# eagle8.net
KiCad netlist of a schematic drawn in EAGLE
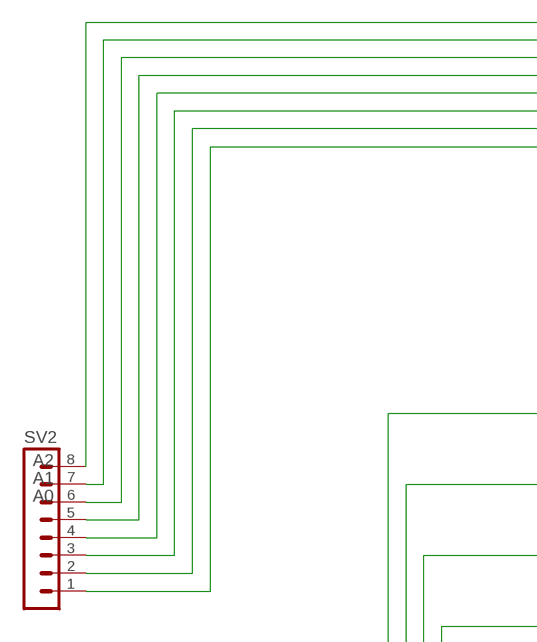
[diagram p0: schematic, sheet 1, part 1 of 3]
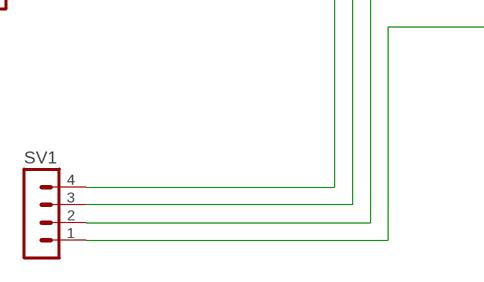
[diagram p1: schematic, sheet 1, part 2 of 3]
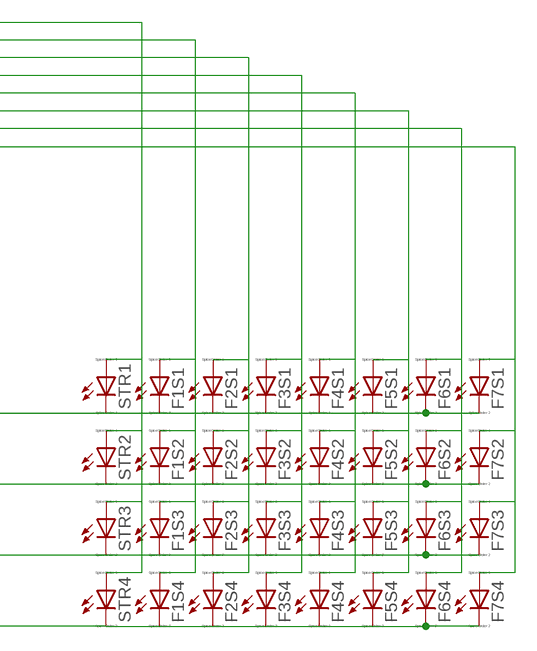
[diagram p2: schematic, sheet 1, part 3 of 3]

(export (version "E")
  (design (tool "Eeschema 10.0.6"))
  (components
    (comp (ref "F1S1")
      (value "LED_ESML0603")
      (footprint "eagle-import:LED_SML0603")
      (libsource (lib "eagle-import") (part "LED_ESML0603"))
    )
    (comp (ref "F1S2")
      (value "LED_ESML0603")
      (footprint "eagle-import:LED_SML0603")
      (libsource (lib "eagle-import") (part "LED_ESML0603"))
    )
    (comp (ref "F1S3")
      (value "LED_ESML0603")
      (footprint "eagle-import:LED_SML0603")
      (libsource (lib "eagle-import") (part "LED_ESML0603"))
    )
    (comp (ref "F1S4")
      (value "LED_ESML0603")
      (footprint "eagle-import:LED_SML0603")
      (libsource (lib "eagle-import") (part "LED_ESML0603"))
    )
    (comp (ref "F2S1")
      (value "LED_ESML0603")
      (footprint "eagle-import:LED_SML0603")
      (libsource (lib "eagle-import") (part "LED_ESML0603"))
    )
    (comp (ref "F2S2")
      (value "LED_ESML0603")
      (footprint "eagle-import:LED_SML0603")
      (libsource (lib "eagle-import") (part "LED_ESML0603"))
    )
    (comp (ref "F2S3")
      (value "LED_ESML0603")
      (footprint "eagle-import:LED_SML0603")
      (libsource (lib "eagle-import") (part "LED_ESML0603"))
    )
    (comp (ref "F2S4")
      (value "LED_ESML0603")
      (footprint "eagle-import:LED_SML0603")
      (libsource (lib "eagle-import") (part "LED_ESML0603"))
    )
    (comp (ref "F3S1")
      (value "LED_ESML0603")
      (footprint "eagle-import:LED_SML0603")
      (libsource (lib "eagle-import") (part "LED_ESML0603"))
    )
    (comp (ref "F3S2")
      (value "LED_ESML0603")
      (footprint "eagle-import:LED_SML0603")
      (libsource (lib "eagle-import") (part "LED_ESML0603"))
    )
    (comp (ref "F3S3")
      (value "LED_ESML0603")
      (footprint "eagle-import:LED_SML0603")
      (libsource (lib "eagle-import") (part "LED_ESML0603"))
    )
    (comp (ref "F3S4")
      (value "LED_ESML0603")
      (footprint "eagle-import:LED_SML0603")
      (libsource (lib "eagle-import") (part "LED_ESML0603"))
    )
    (comp (ref "F4S1")
      (value "LED_ESML0603")
      (footprint "eagle-import:LED_SML0603")
      (libsource (lib "eagle-import") (part "LED_ESML0603"))
    )
    (comp (ref "F4S2")
      (value "LED_ESML0603")
      (footprint "eagle-import:LED_SML0603")
      (libsource (lib "eagle-import") (part "LED_ESML0603"))
    )
    (comp (ref "F4S3")
      (value "LED_ESML0603")
      (footprint "eagle-import:LED_SML0603")
      (libsource (lib "eagle-import") (part "LED_ESML0603"))
    )
    (comp (ref "F4S4")
      (value "LED_ESML0603")
      (footprint "eagle-import:LED_SML0603")
      (libsource (lib "eagle-import") (part "LED_ESML0603"))
    )
    (comp (ref "F5S1")
      (value "LED_ESML0603")
      (footprint "eagle-import:LED_SML0603")
      (libsource (lib "eagle-import") (part "LED_ESML0603"))
    )
    (comp (ref "F5S2")
      (value "LED_ESML0603")
      (footprint "eagle-import:LED_SML0603")
      (libsource (lib "eagle-import") (part "LED_ESML0603"))
    )
    (comp (ref "F5S3")
      (value "LED_ESML0603")
      (footprint "eagle-import:LED_SML0603")
      (libsource (lib "eagle-import") (part "LED_ESML0603"))
    )
    (comp (ref "F5S4")
      (value "LED_ESML0603")
      (footprint "eagle-import:LED_SML0603")
      (libsource (lib "eagle-import") (part "LED_ESML0603"))
    )
    (comp (ref "F6S1")
      (value "LED_ESML0603")
      (footprint "eagle-import:LED_SML0603")
      (libsource (lib "eagle-import") (part "LED_ESML0603"))
    )
    (comp (ref "F6S2")
      (value "LED_ESML0603")
      (footprint "eagle-import:LED_SML0603")
      (libsource (lib "eagle-import") (part "LED_ESML0603"))
    )
    (comp (ref "F6S3")
      (value "LED_ESML0603")
      (footprint "eagle-import:LED_SML0603")
      (libsource (lib "eagle-import") (part "LED_ESML0603"))
    )
    (comp (ref "F6S4")
      (value "LED_ESML0603")
      (footprint "eagle-import:LED_SML0603")
      (libsource (lib "eagle-import") (part "LED_ESML0603"))
    )
    (comp (ref "F7S1")
      (value "LED_ESML0603")
      (footprint "eagle-import:LED_SML0603")
      (libsource (lib "eagle-import") (part "LED_ESML0603"))
    )
    (comp (ref "F7S2")
      (value "LED_ESML0603")
      (footprint "eagle-import:LED_SML0603")
      (libsource (lib "eagle-import") (part "LED_ESML0603"))
    )
    (comp (ref "F7S3")
      (value "LED_ESML0603")
      (footprint "eagle-import:LED_SML0603")
      (libsource (lib "eagle-import") (part "LED_ESML0603"))
    )
    (comp (ref "F7S4")
      (value "LED_ESML0603")
      (footprint "eagle-import:LED_SML0603")
      (libsource (lib "eagle-import") (part "LED_ESML0603"))
    )
    (comp (ref "STR1")
      (value "LED_ESML0603")
      (footprint "eagle-import:LED_SML0603")
      (libsource (lib "eagle-import") (part "LED_ESML0603"))
    )
    (comp (ref "STR2")
      (value "LED_ESML0603")
      (footprint "eagle-import:LED_SML0603")
      (libsource (lib "eagle-import") (part "LED_ESML0603"))
    )
    (comp (ref "STR3")
      (value "LED_ESML0603")
      (footprint "eagle-import:LED_SML0603")
      (libsource (lib "eagle-import") (part "LED_ESML0603"))
    )
    (comp (ref "STR4")
      (value "LED_ESML0603")
      (footprint "eagle-import:LED_SML0603")
      (libsource (lib "eagle-import") (part "LED_ESML0603"))
    )
    (comp (ref "SV1")
      (value "MA04-1")
      (footprint "eagle-import:MA04-1")
      (libsource (lib "eagle-import") (part "MA04-1"))
    )
    (comp (ref "SV2")
      (value "MA08-1")
      (footprint "eagle-import:MA08-1")
      (libsource (lib "eagle-import") (part "MA08-1"))
    )
  )
  (nets
    (net (code "1") (name "/A0") (class "Default")
      (node (ref "F2S1") (pin "A") (pinfunction "A_A") (pintype "passive"))
      (node (ref "F2S2") (pin "A") (pinfunction "A_A") (pintype "passive"))
      (node (ref "F2S3") (pin "A") (pinfunction "A_A") (pintype "passive"))
      (node (ref "F2S4") (pin "A") (pinfunction "A_A") (pintype "passive"))
      (node (ref "SV2") (pin "6") (pinfunction "6_6") (pintype "passive"))
    )
    (net (code "2") (name "/A1") (class "Default")
      (node (ref "F1S1") (pin "A") (pinfunction "A_A") (pintype "passive"))
      (node (ref "F1S2") (pin "A") (pinfunction "A_A") (pintype "passive"))
      (node (ref "F1S3") (pin "A") (pinfunction "A_A") (pintype "passive"))
      (node (ref "F1S4") (pin "A") (pinfunction "A_A") (pintype "passive"))
      (node (ref "SV2") (pin "7") (pinfunction "7_7") (pintype "passive"))
    )
    (net (code "3") (name "/A2") (class "Default")
      (node (ref "STR1") (pin "A") (pinfunction "A_A") (pintype "passive"))
      (node (ref "STR2") (pin "A") (pinfunction "A_A") (pintype "passive"))
      (node (ref "STR3") (pin "A") (pinfunction "A_A") (pintype "passive"))
      (node (ref "STR4") (pin "A") (pinfunction "A_A") (pintype "passive"))
      (node (ref "SV2") (pin "8") (pinfunction "8_8") (pintype "passive"))
    )
    (net (code "4") (name "Net-(F1S1-PadC)") (class "Default")
      (node (ref "F1S1") (pin "C") (pinfunction "C_C") (pintype "passive"))
      (node (ref "F2S1") (pin "C") (pinfunction "C_C") (pintype "passive"))
      (node (ref "F3S1") (pin "C") (pinfunction "C_C") (pintype "passive"))
      (node (ref "F4S1") (pin "C") (pinfunction "C_C") (pintype "passive"))
      (node (ref "F5S1") (pin "C") (pinfunction "C_C") (pintype "passive"))
      (node (ref "F6S1") (pin "C") (pinfunction "C_C") (pintype "passive"))
      (node (ref "F7S1") (pin "C") (pinfunction "C_C") (pintype "passive"))
      (node (ref "STR1") (pin "C") (pinfunction "C_C") (pintype "passive"))
      (node (ref "SV1") (pin "4") (pinfunction "4_4") (pintype "passive"))
    )
    (net (code "5") (name "Net-(F1S2-PadC)") (class "Default")
      (node (ref "F1S2") (pin "C") (pinfunction "C_C") (pintype "passive"))
      (node (ref "F2S2") (pin "C") (pinfunction "C_C") (pintype "passive"))
      (node (ref "F3S2") (pin "C") (pinfunction "C_C") (pintype "passive"))
      (node (ref "F4S2") (pin "C") (pinfunction "C_C") (pintype "passive"))
      (node (ref "F5S2") (pin "C") (pinfunction "C_C") (pintype "passive"))
      (node (ref "F6S2") (pin "C") (pinfunction "C_C") (pintype "passive"))
      (node (ref "F7S2") (pin "C") (pinfunction "C_C") (pintype "passive"))
      (node (ref "STR2") (pin "C") (pinfunction "C_C") (pintype "passive"))
      (node (ref "SV1") (pin "3") (pinfunction "3_3") (pintype "passive"))
    )
    (net (code "6") (name "Net-(F1S3-PadC)") (class "Default")
      (node (ref "F1S3") (pin "C") (pinfunction "C_C") (pintype "passive"))
      (node (ref "F2S3") (pin "C") (pinfunction "C_C") (pintype "passive"))
      (node (ref "F3S3") (pin "C") (pinfunction "C_C") (pintype "passive"))
      (node (ref "F4S3") (pin "C") (pinfunction "C_C") (pintype "passive"))
      (node (ref "F5S3") (pin "C") (pinfunction "C_C") (pintype "passive"))
      (node (ref "F6S3") (pin "C") (pinfunction "C_C") (pintype "passive"))
      (node (ref "F7S3") (pin "C") (pinfunction "C_C") (pintype "passive"))
      (node (ref "STR3") (pin "C") (pinfunction "C_C") (pintype "passive"))
      (node (ref "SV1") (pin "2") (pinfunction "2_2") (pintype "passive"))
    )
    (net (code "7") (name "Net-(F1S4-PadC)") (class "Default")
      (node (ref "F1S4") (pin "C") (pinfunction "C_C") (pintype "passive"))
      (node (ref "F2S4") (pin "C") (pinfunction "C_C") (pintype "passive"))
      (node (ref "F3S4") (pin "C") (pinfunction "C_C") (pintype "passive"))
      (node (ref "F4S4") (pin "C") (pinfunction "C_C") (pintype "passive"))
      (node (ref "F5S4") (pin "C") (pinfunction "C_C") (pintype "passive"))
      (node (ref "F6S4") (pin "C") (pinfunction "C_C") (pintype "passive"))
      (node (ref "F7S4") (pin "C") (pinfunction "C_C") (pintype "passive"))
      (node (ref "STR4") (pin "C") (pinfunction "C_C") (pintype "passive"))
      (node (ref "SV1") (pin "1") (pinfunction "1_1") (pintype "passive"))
    )
    (net (code "8") (name "Net-(F3S1-PadA)") (class "Default")
      (node (ref "F3S1") (pin "A") (pinfunction "A_A") (pintype "passive"))
      (node (ref "F3S2") (pin "A") (pinfunction "A_A") (pintype "passive"))
      (node (ref "F3S3") (pin "A") (pinfunction "A_A") (pintype "passive"))
      (node (ref "F3S4") (pin "A") (pinfunction "A_A") (pintype "passive"))
      (node (ref "SV2") (pin "5") (pinfunction "5_5") (pintype "passive"))
    )
    (net (code "9") (name "Net-(F4S1-PadA)") (class "Default")
      (node (ref "F4S1") (pin "A") (pinfunction "A_A") (pintype "passive"))
      (node (ref "F4S2") (pin "A") (pinfunction "A_A") (pintype "passive"))
      (node (ref "F4S3") (pin "A") (pinfunction "A_A") (pintype "passive"))
      (node (ref "F4S4") (pin "A") (pinfunction "A_A") (pintype "passive"))
      (node (ref "SV2") (pin "4") (pinfunction "4_4") (pintype "passive"))
    )
    (net (code "10") (name "Net-(F5S1-PadA)") (class "Default")
      (node (ref "F5S1") (pin "A") (pinfunction "A_A") (pintype "passive"))
      (node (ref "F5S2") (pin "A") (pinfunction "A_A") (pintype "passive"))
      (node (ref "F5S3") (pin "A") (pinfunction "A_A") (pintype "passive"))
      (node (ref "F5S4") (pin "A") (pinfunction "A_A") (pintype "passive"))
      (node (ref "SV2") (pin "3") (pinfunction "3_3") (pintype "passive"))
    )
    (net (code "11") (name "Net-(F6S1-PadA)") (class "Default")
      (node (ref "F6S1") (pin "A") (pinfunction "A_A") (pintype "passive"))
      (node (ref "F6S2") (pin "A") (pinfunction "A_A") (pintype "passive"))
      (node (ref "F6S3") (pin "A") (pinfunction "A_A") (pintype "passive"))
      (node (ref "F6S4") (pin "A") (pinfunction "A_A") (pintype "passive"))
      (node (ref "SV2") (pin "2") (pinfunction "2_2") (pintype "passive"))
    )
    (net (code "12") (name "Net-(F7S1-PadA)") (class "Default")
      (node (ref "F7S1") (pin "A") (pinfunction "A_A") (pintype "passive"))
      (node (ref "F7S2") (pin "A") (pinfunction "A_A") (pintype "passive"))
      (node (ref "F7S3") (pin "A") (pinfunction "A_A") (pintype "passive"))
      (node (ref "F7S4") (pin "A") (pinfunction "A_A") (pintype "passive"))
      (node (ref "SV2") (pin "1") (pinfunction "1_1") (pintype "passive"))
    )
  )
)
